# SD_CARD.net
KiCad netlist of a schematic drawn in Altium Designer
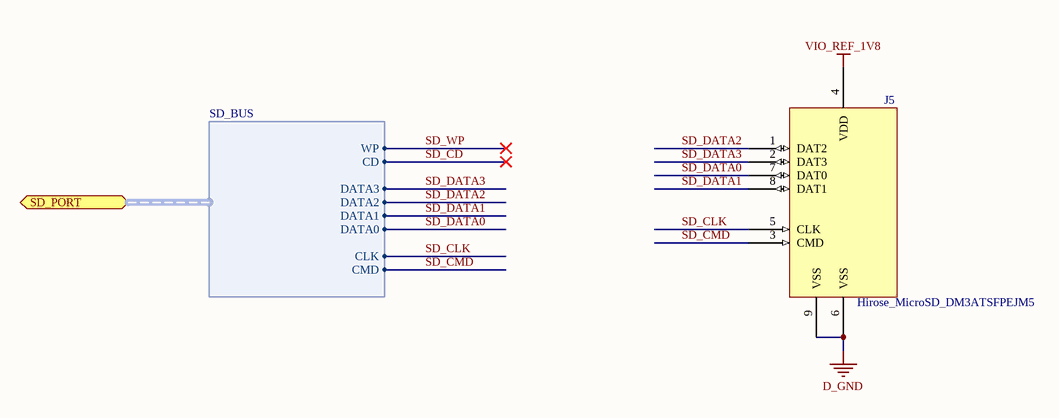
[diagram p0: SD_CARD.SchDoc]

(export (version "E")
  (design (tool "Eeschema 10.0.6"))
  (components
    (comp (ref "J5")
      (value "Hirose_MicroSD_DM3ATSFPEJM5")
      (footprint "SD_CARD_Micro_Hirose:SD_Card_Hirose_DM3 AT_SF_PEJM5")
      (libsource (lib "SD_Card_Micro") (part "Component_1"))
    )
  )
  (nets
    (net (code "3") (name "/SD_CLK") (class "Default")
      (node (ref "J5") (pin "5") (pinfunction "CLK_5") (pintype "input"))
    )
    (net (code "4") (name "/SD_CMD") (class "Default")
      (node (ref "J5") (pin "3") (pinfunction "CMD_3") (pintype "input"))
    )
    (net (code "5") (name "/SD_DATA0") (class "Default")
      (node (ref "J5") (pin "7") (pinfunction "DAT0_7") (pintype "bidirectional"))
    )
    (net (code "6") (name "/SD_DATA1") (class "Default")
      (node (ref "J5") (pin "8") (pinfunction "DAT1_8") (pintype "bidirectional"))
    )
    (net (code "7") (name "/SD_DATA2") (class "Default")
      (node (ref "J5") (pin "1") (pinfunction "DAT2_1") (pintype "bidirectional"))
    )
    (net (code "8") (name "/SD_DATA3") (class "Default")
      (node (ref "J5") (pin "2") (pinfunction "DAT3_2") (pintype "bidirectional"))
    )
    (net (code "11") (name "D_GND") (class "Default")
      (node (ref "J5") (pin "6") (pinfunction "VSS_6") (pintype "power_in"))
      (node (ref "J5") (pin "9") (pinfunction "VSS_9") (pintype "power_in"))
    )
    (net (code "12") (name "VIO_REF_1V8") (class "Default")
      (node (ref "J5") (pin "4") (pinfunction "VDD_4") (pintype "power_in"))
    )
  )
)
